# ECU_Checker_New.net
KiCad netlist of a schematic drawn in EAGLE
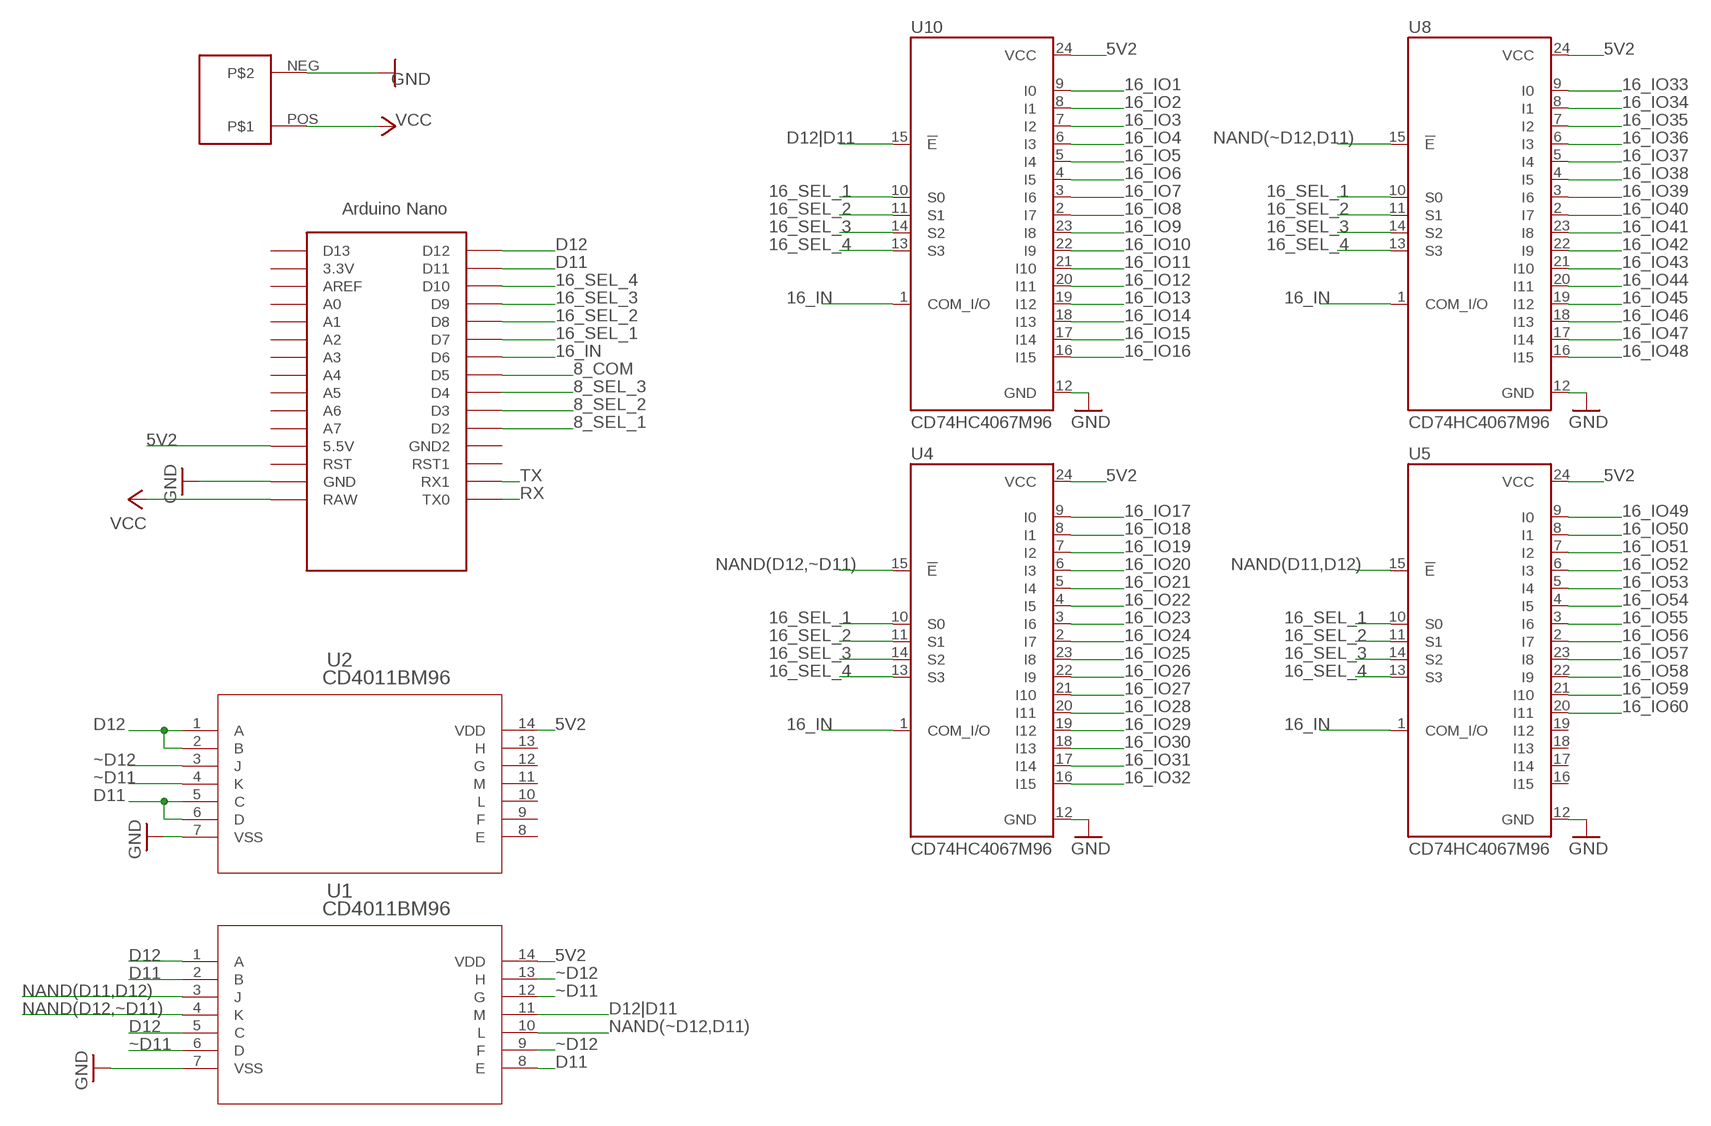
[diagram p0: schematic, sheet 1, part 1 of 2]
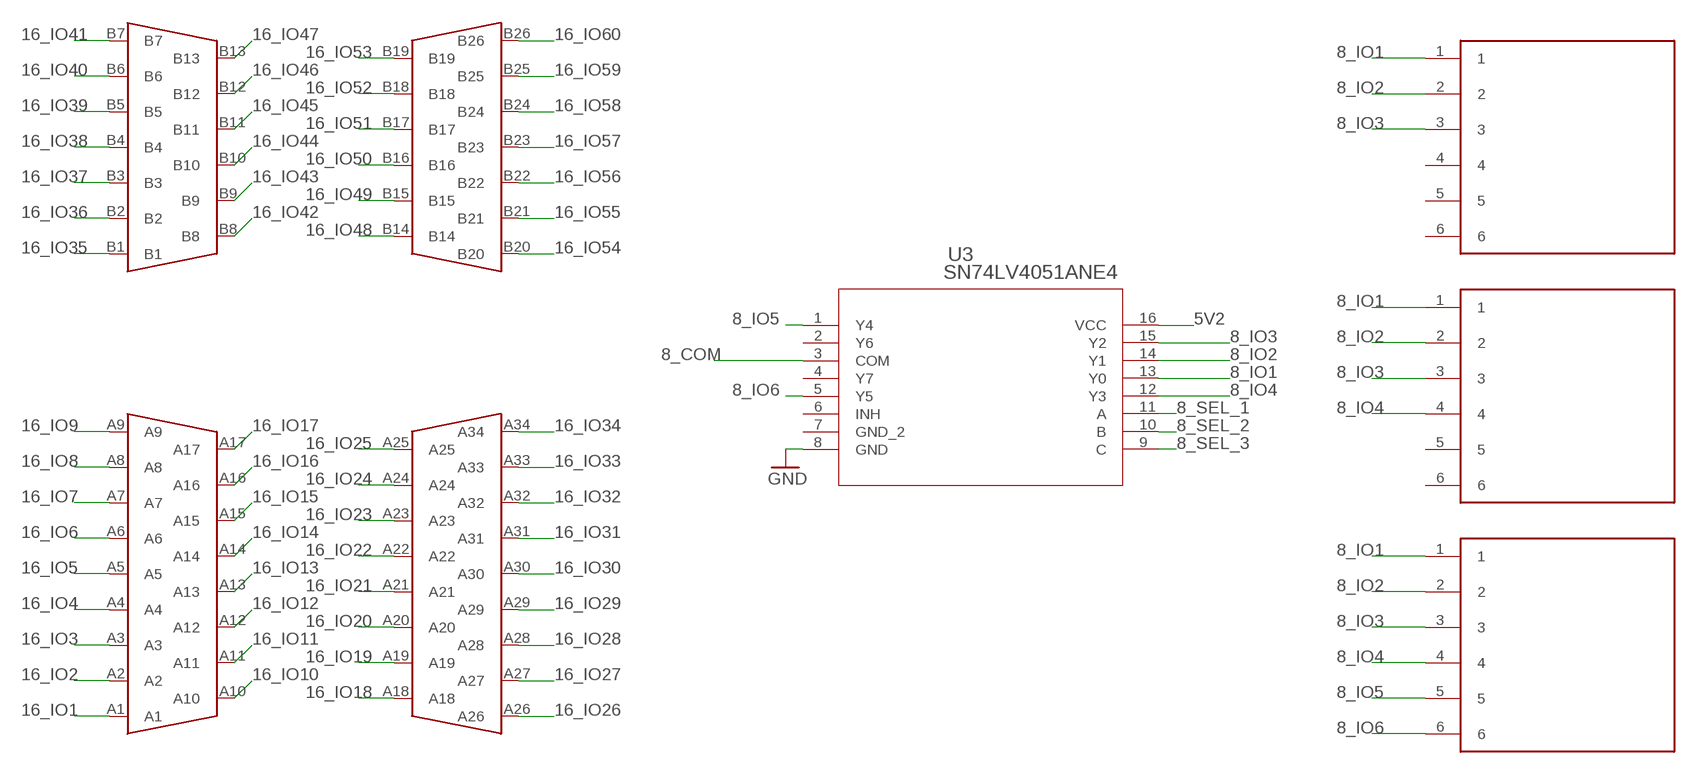
[diagram p1: schematic, sheet 1, part 2 of 2]

(export (version "E")
  (design (tool "Eeschema 10.0.6"))
  (components
    (comp (ref "U$2")
      (value "NANO")
      (footprint "eagle-import:NANO")
      (libsource (lib "eagle-import") (part "NANO"))
    )
    (comp (ref "U$3")
      (value "DTM_CON")
      (footprint "eagle-import:DTM_CON_F")
      (libsource (lib "eagle-import") (part "DTM_CON"))
    )
    (comp (ref "U$4")
      (value "BATTERY")
      (footprint "eagle-import:BATTERY_F")
      (libsource (lib "eagle-import") (part "BATTERY"))
    )
    (comp (ref "U$5")
      (value "DTM_CON")
      (footprint "eagle-import:DTM_CON_F")
      (libsource (lib "eagle-import") (part "DTM_CON"))
    )
    (comp (ref "U$6")
      (value "DTM_CON")
      (footprint "eagle-import:DTM_CON_F")
      (libsource (lib "eagle-import") (part "DTM_CON"))
    )
    (comp (ref "U$7")
      (value "MOTEC_400_CON")
      (footprint "eagle-import:MOTEC_400_CON_F")
      (libsource (lib "eagle-import") (part "MOTEC_400_CON"))
    )
    (comp (ref "U1")
      (value "CD4011BM96")
      (footprint "eagle-import:D14")
      (libsource (lib "eagle-import") (part "CD4011BM96"))
    )
    (comp (ref "U2")
      (value "CD4011BM96")
      (footprint "eagle-import:D14")
      (libsource (lib "eagle-import") (part "CD4011BM96"))
    )
    (comp (ref "U3")
      (value "SN74LV4051ANE4")
      (footprint "eagle-import:N16")
      (libsource (lib "eagle-import") (part "SN74LV4051ANE4"))
    )
    (comp (ref "U4")
      (value "CD74HC4067M96")
      (footprint "eagle-import:SOIC127P1030X265-24N")
      (fields (field (name "MF") "Texas Instruments"))
      (libsource (lib "eagle-import") (part "CD74HC4067M96"))
    )
    (comp (ref "U5")
      (value "CD74HC4067M96")
      (footprint "eagle-import:SOIC127P1030X265-24N")
      (fields (field (name "MF") "Texas Instruments"))
      (libsource (lib "eagle-import") (part "CD74HC4067M96"))
    )
    (comp (ref "U8")
      (value "CD74HC4067M96")
      (footprint "eagle-import:SOIC127P1030X265-24N")
      (fields (field (name "MF") "Texas Instruments"))
      (libsource (lib "eagle-import") (part "CD74HC4067M96"))
    )
    (comp (ref "U10")
      (value "CD74HC4067M96")
      (footprint "eagle-import:SOIC127P1030X265-24N")
      (fields (field (name "MF") "Texas Instruments"))
      (libsource (lib "eagle-import") (part "CD74HC4067M96"))
    )
  )
  (nets
    (net (code "1") (name "/5V2") (class "Default")
      (node (ref "U$2") (pin "5V") (pinfunction "5.5V_5V") (pintype "bidirectional"))
      (node (ref "U1") (pin "14") (pinfunction "VDD_14") (pintype "passive"))
      (node (ref "U10") (pin "24") (pinfunction "VCC_24") (pintype "power_in"))
      (node (ref "U2") (pin "14") (pinfunction "VDD_14") (pintype "passive"))
      (node (ref "U3") (pin "16") (pinfunction "VCC_16") (pintype "power_in"))
      (node (ref "U4") (pin "24") (pinfunction "VCC_24") (pintype "power_in"))
      (node (ref "U5") (pin "24") (pinfunction "VCC_24") (pintype "power_in"))
      (node (ref "U8") (pin "24") (pinfunction "VCC_24") (pintype "power_in"))
    )
    (net (code "2") (name "/8_COM") (class "Default")
      (node (ref "U$2") (pin "D5") (pinfunction "D5_D5") (pintype "bidirectional"))
      (node (ref "U3") (pin "3") (pinfunction "COM_3") (pintype "input"))
    )
    (net (code "3") (name "/8_IO1") (class "Default")
      (node (ref "U$3") (pin "1") (pinfunction "1_1") (pintype "bidirectional"))
      (node (ref "U$5") (pin "1") (pinfunction "1_1") (pintype "bidirectional"))
      (node (ref "U$6") (pin "1") (pinfunction "1_1") (pintype "bidirectional"))
      (node (ref "U3") (pin "13") (pinfunction "Y0_13") (pintype "output"))
    )
    (net (code "4") (name "/8_IO2") (class "Default")
      (node (ref "U$3") (pin "2") (pinfunction "2_2") (pintype "bidirectional"))
      (node (ref "U$5") (pin "2") (pinfunction "2_2") (pintype "bidirectional"))
      (node (ref "U$6") (pin "2") (pinfunction "2_2") (pintype "bidirectional"))
      (node (ref "U3") (pin "14") (pinfunction "Y1_14") (pintype "output"))
    )
    (net (code "5") (name "/8_IO3") (class "Default")
      (node (ref "U$3") (pin "3") (pinfunction "3_3") (pintype "bidirectional"))
      (node (ref "U$5") (pin "3") (pinfunction "3_3") (pintype "bidirectional"))
      (node (ref "U$6") (pin "3") (pinfunction "3_3") (pintype "bidirectional"))
      (node (ref "U3") (pin "15") (pinfunction "Y2_15") (pintype "output"))
    )
    (net (code "6") (name "/8_IO4") (class "Default")
      (node (ref "U$5") (pin "4") (pinfunction "4_4") (pintype "bidirectional"))
      (node (ref "U$6") (pin "4") (pinfunction "4_4") (pintype "bidirectional"))
      (node (ref "U3") (pin "12") (pinfunction "Y3_12") (pintype "output"))
    )
    (net (code "7") (name "/8_IO5") (class "Default")
      (node (ref "U$6") (pin "5") (pinfunction "5_5") (pintype "bidirectional"))
      (node (ref "U3") (pin "1") (pinfunction "Y4_1") (pintype "output"))
    )
    (net (code "8") (name "/8_IO6") (class "Default")
      (node (ref "U$6") (pin "6") (pinfunction "6_6") (pintype "bidirectional"))
      (node (ref "U3") (pin "5") (pinfunction "Y5_5") (pintype "output"))
    )
    (net (code "9") (name "/8_SEL_1") (class "Default")
      (node (ref "U$2") (pin "D2") (pinfunction "D2_D2") (pintype "bidirectional"))
      (node (ref "U3") (pin "11") (pinfunction "A_11") (pintype "input"))
    )
    (net (code "10") (name "/8_SEL_2") (class "Default")
      (node (ref "U$2") (pin "D3") (pinfunction "D3_D3") (pintype "bidirectional"))
      (node (ref "U3") (pin "10") (pinfunction "B_10") (pintype "input"))
    )
    (net (code "11") (name "/8_SEL_3") (class "Default")
      (node (ref "U$2") (pin "D4") (pinfunction "D4_D4") (pintype "bidirectional"))
      (node (ref "U3") (pin "9") (pinfunction "C_9") (pintype "input"))
    )
    (net (code "12") (name "/16_IN") (class "Default")
      (node (ref "U$2") (pin "D6") (pinfunction "D6_D6") (pintype "bidirectional"))
      (node (ref "U10") (pin "1") (pinfunction "COM_I/O_1") (pintype "bidirectional"))
      (node (ref "U4") (pin "1") (pinfunction "COM_I/O_1") (pintype "bidirectional"))
      (node (ref "U5") (pin "1") (pinfunction "COM_I/O_1") (pintype "bidirectional"))
      (node (ref "U8") (pin "1") (pinfunction "COM_I/O_1") (pintype "bidirectional"))
    )
    (net (code "13") (name "/16_IO1") (class "Default")
      (node (ref "U$7") (pin "A1") (pinfunction "A1_A1") (pintype "bidirectional"))
      (node (ref "U10") (pin "9") (pinfunction "I0_9") (pintype "bidirectional"))
    )
    (net (code "14") (name "/16_IO2") (class "Default")
      (node (ref "U$7") (pin "A2") (pinfunction "A2_A2") (pintype "bidirectional"))
      (node (ref "U10") (pin "8") (pinfunction "I1_8") (pintype "bidirectional"))
    )
    (net (code "15") (name "/16_IO3") (class "Default")
      (node (ref "U$7") (pin "A3") (pinfunction "A3_A3") (pintype "bidirectional"))
      (node (ref "U10") (pin "7") (pinfunction "I2_7") (pintype "bidirectional"))
    )
    (net (code "16") (name "/16_IO4") (class "Default")
      (node (ref "U$7") (pin "A4") (pinfunction "A4_A4") (pintype "bidirectional"))
      (node (ref "U10") (pin "6") (pinfunction "I3_6") (pintype "bidirectional"))
    )
    (net (code "17") (name "/16_IO5") (class "Default")
      (node (ref "U$7") (pin "A5") (pinfunction "A5_A5") (pintype "bidirectional"))
      (node (ref "U10") (pin "5") (pinfunction "I4_5") (pintype "bidirectional"))
    )
    (net (code "18") (name "/16_IO6") (class "Default")
      (node (ref "U$7") (pin "A6") (pinfunction "A6_A6") (pintype "bidirectional"))
      (node (ref "U10") (pin "4") (pinfunction "I5_4") (pintype "bidirectional"))
    )
    (net (code "19") (name "/16_IO7") (class "Default")
      (node (ref "U$7") (pin "A7") (pinfunction "A7_A7") (pintype "bidirectional"))
      (node (ref "U10") (pin "3") (pinfunction "I6_3") (pintype "bidirectional"))
    )
    (net (code "20") (name "/16_IO8") (class "Default")
      (node (ref "U$7") (pin "A8") (pinfunction "A8_A8") (pintype "bidirectional"))
      (node (ref "U10") (pin "2") (pinfunction "I7_2") (pintype "bidirectional"))
    )
    (net (code "21") (name "/16_IO9") (class "Default")
      (node (ref "U$7") (pin "A9") (pinfunction "A9_A9") (pintype "bidirectional"))
      (node (ref "U10") (pin "23") (pinfunction "I8_23") (pintype "bidirectional"))
    )
    (net (code "22") (name "/16_IO10") (class "Default")
      (node (ref "U$7") (pin "A10") (pinfunction "A10_A10") (pintype "bidirectional"))
      (node (ref "U10") (pin "22") (pinfunction "I9_22") (pintype "bidirectional"))
    )
    (net (code "23") (name "/16_IO11") (class "Default")
      (node (ref "U$7") (pin "A11") (pinfunction "A11_A11") (pintype "bidirectional"))
      (node (ref "U10") (pin "21") (pinfunction "I10_21") (pintype "bidirectional"))
    )
    (net (code "24") (name "/16_IO12") (class "Default")
      (node (ref "U$7") (pin "A12") (pinfunction "A12_A12") (pintype "bidirectional"))
      (node (ref "U10") (pin "20") (pinfunction "I11_20") (pintype "bidirectional"))
    )
    (net (code "25") (name "/16_IO13") (class "Default")
      (node (ref "U$7") (pin "A13") (pinfunction "A13_A13") (pintype "bidirectional"))
      (node (ref "U10") (pin "19") (pinfunction "I12_19") (pintype "bidirectional"))
    )
    (net (code "26") (name "/16_IO14") (class "Default")
      (node (ref "U$7") (pin "A14") (pinfunction "A14_A14") (pintype "bidirectional"))
      (node (ref "U10") (pin "18") (pinfunction "I13_18") (pintype "bidirectional"))
    )
    (net (code "27") (name "/16_IO15") (class "Default")
      (node (ref "U$7") (pin "A15") (pinfunction "A15_A15") (pintype "bidirectional"))
      (node (ref "U10") (pin "17") (pinfunction "I14_17") (pintype "bidirectional"))
    )
    (net (code "28") (name "/16_IO16") (class "Default")
      (node (ref "U$7") (pin "A16") (pinfunction "A16_A16") (pintype "bidirectional"))
      (node (ref "U10") (pin "16") (pinfunction "I15_16") (pintype "bidirectional"))
    )
    (net (code "29") (name "/16_IO17") (class "Default")
      (node (ref "U$7") (pin "A17") (pinfunction "A17_A17") (pintype "bidirectional"))
      (node (ref "U4") (pin "9") (pinfunction "I0_9") (pintype "bidirectional"))
    )
    (net (code "30") (name "/16_IO18") (class "Default")
      (node (ref "U$7") (pin "A18") (pinfunction "A18_A18") (pintype "bidirectional"))
      (node (ref "U4") (pin "8") (pinfunction "I1_8") (pintype "bidirectional"))
    )
    (net (code "31") (name "/16_IO19") (class "Default")
      (node (ref "U$7") (pin "A19") (pinfunction "A19_A19") (pintype "bidirectional"))
      (node (ref "U4") (pin "7") (pinfunction "I2_7") (pintype "bidirectional"))
    )
    (net (code "32") (name "/16_IO20") (class "Default")
      (node (ref "U$7") (pin "A20") (pinfunction "A20_A20") (pintype "bidirectional"))
      (node (ref "U4") (pin "6") (pinfunction "I3_6") (pintype "bidirectional"))
    )
    (net (code "33") (name "/16_IO21") (class "Default")
      (node (ref "U$7") (pin "A21") (pinfunction "A21_A21") (pintype "bidirectional"))
      (node (ref "U4") (pin "5") (pinfunction "I4_5") (pintype "bidirectional"))
    )
    (net (code "34") (name "/16_IO22") (class "Default")
      (node (ref "U$7") (pin "A22") (pinfunction "A22_A22") (pintype "bidirectional"))
      (node (ref "U4") (pin "4") (pinfunction "I5_4") (pintype "bidirectional"))
    )
    (net (code "35") (name "/16_IO23") (class "Default")
      (node (ref "U$7") (pin "A23") (pinfunction "A23_A23") (pintype "bidirectional"))
      (node (ref "U4") (pin "3") (pinfunction "I6_3") (pintype "bidirectional"))
    )
    (net (code "36") (name "/16_IO24") (class "Default")
      (node (ref "U$7") (pin "A24") (pinfunction "A24_A24") (pintype "bidirectional"))
      (node (ref "U4") (pin "2") (pinfunction "I7_2") (pintype "bidirectional"))
    )
    (net (code "37") (name "/16_IO25") (class "Default")
      (node (ref "U$7") (pin "A25") (pinfunction "A25_A25") (pintype "bidirectional"))
      (node (ref "U4") (pin "23") (pinfunction "I8_23") (pintype "bidirectional"))
    )
    (net (code "38") (name "/16_IO26") (class "Default")
      (node (ref "U$7") (pin "A26") (pinfunction "A26_A26") (pintype "bidirectional"))
      (node (ref "U4") (pin "22") (pinfunction "I9_22") (pintype "bidirectional"))
    )
    (net (code "39") (name "/16_IO27") (class "Default")
      (node (ref "U$7") (pin "A27") (pinfunction "A27_A27") (pintype "bidirectional"))
      (node (ref "U4") (pin "21") (pinfunction "I10_21") (pintype "bidirectional"))
    )
    (net (code "40") (name "/16_IO28") (class "Default")
      (node (ref "U$7") (pin "A28") (pinfunction "A28_A28") (pintype "bidirectional"))
      (node (ref "U4") (pin "20") (pinfunction "I11_20") (pintype "bidirectional"))
    )
    (net (code "41") (name "/16_IO29") (class "Default")
      (node (ref "U$7") (pin "A29") (pinfunction "A29_A29") (pintype "bidirectional"))
      (node (ref "U4") (pin "19") (pinfunction "I12_19") (pintype "bidirectional"))
    )
    (net (code "42") (name "/16_IO30") (class "Default")
      (node (ref "U$7") (pin "A30") (pinfunction "A30_A30") (pintype "bidirectional"))
      (node (ref "U4") (pin "18") (pinfunction "I13_18") (pintype "bidirectional"))
    )
    (net (code "43") (name "/16_IO31") (class "Default")
      (node (ref "U$7") (pin "A31") (pinfunction "A31_A31") (pintype "bidirectional"))
      (node (ref "U4") (pin "17") (pinfunction "I14_17") (pintype "bidirectional"))
    )
    (net (code "44") (name "/16_IO32") (class "Default")
      (node (ref "U$7") (pin "A32") (pinfunction "A32_A32") (pintype "bidirectional"))
      (node (ref "U4") (pin "16") (pinfunction "I15_16") (pintype "bidirectional"))
    )
    (net (code "45") (name "/16_IO33") (class "Default")
      (node (ref "U$7") (pin "A33") (pinfunction "A33_A33") (pintype "bidirectional"))
      (node (ref "U8") (pin "9") (pinfunction "I0_9") (pintype "bidirectional"))
    )
    (net (code "46") (name "/16_IO34") (class "Default")
      (node (ref "U$7") (pin "A34") (pinfunction "A34_A34") (pintype "bidirectional"))
      (node (ref "U8") (pin "8") (pinfunction "I1_8") (pintype "bidirectional"))
    )
    (net (code "47") (name "/16_IO35") (class "Default")
      (node (ref "U$7") (pin "B1") (pinfunction "B1_B1") (pintype "bidirectional"))
      (node (ref "U8") (pin "7") (pinfunction "I2_7") (pintype "bidirectional"))
    )
    (net (code "48") (name "/16_IO36") (class "Default")
      (node (ref "U$7") (pin "B2") (pinfunction "B2_B2") (pintype "bidirectional"))
      (node (ref "U8") (pin "6") (pinfunction "I3_6") (pintype "bidirectional"))
    )
    (net (code "49") (name "/16_IO37") (class "Default")
      (node (ref "U$7") (pin "B3") (pinfunction "B3_B3") (pintype "bidirectional"))
      (node (ref "U8") (pin "5") (pinfunction "I4_5") (pintype "bidirectional"))
    )
    (net (code "50") (name "/16_IO38") (class "Default")
      (node (ref "U$7") (pin "B4") (pinfunction "B4_B4") (pintype "bidirectional"))
      (node (ref "U8") (pin "4") (pinfunction "I5_4") (pintype "bidirectional"))
    )
    (net (code "51") (name "/16_IO39") (class "Default")
      (node (ref "U$7") (pin "B5") (pinfunction "B5_B5") (pintype "bidirectional"))
      (node (ref "U8") (pin "3") (pinfunction "I6_3") (pintype "bidirectional"))
    )
    (net (code "52") (name "/16_IO40") (class "Default")
      (node (ref "U$7") (pin "B6") (pinfunction "B6_B6") (pintype "bidirectional"))
      (node (ref "U8") (pin "2") (pinfunction "I7_2") (pintype "bidirectional"))
    )
    (net (code "53") (name "/16_IO41") (class "Default")
      (node (ref "U$7") (pin "B7") (pinfunction "B7_B7") (pintype "bidirectional"))
      (node (ref "U8") (pin "23") (pinfunction "I8_23") (pintype "bidirectional"))
    )
    (net (code "54") (name "/16_IO42") (class "Default")
      (node (ref "U$7") (pin "B8") (pinfunction "B8_B8") (pintype "bidirectional"))
      (node (ref "U8") (pin "22") (pinfunction "I9_22") (pintype "bidirectional"))
    )
    (net (code "55") (name "/16_IO43") (class "Default")
      (node (ref "U$7") (pin "B9") (pinfunction "B9_B9") (pintype "bidirectional"))
      (node (ref "U8") (pin "21") (pinfunction "I10_21") (pintype "bidirectional"))
    )
    (net (code "56") (name "/16_IO44") (class "Default")
      (node (ref "U$7") (pin "B10") (pinfunction "B10_B10") (pintype "bidirectional"))
      (node (ref "U8") (pin "20") (pinfunction "I11_20") (pintype "bidirectional"))
    )
    (net (code "57") (name "/16_IO45") (class "Default")
      (node (ref "U$7") (pin "B11") (pinfunction "B11_B11") (pintype "bidirectional"))
      (node (ref "U8") (pin "19") (pinfunction "I12_19") (pintype "bidirectional"))
    )
    (net (code "58") (name "/16_IO46") (class "Default")
      (node (ref "U$7") (pin "B12") (pinfunction "B12_B12") (pintype "bidirectional"))
      (node (ref "U8") (pin "18") (pinfunction "I13_18") (pintype "bidirectional"))
    )
    (net (code "59") (name "/16_IO47") (class "Default")
      (node (ref "U$7") (pin "B13") (pinfunction "B13_B13") (pintype "bidirectional"))
      (node (ref "U8") (pin "17") (pinfunction "I14_17") (pintype "bidirectional"))
    )
    (net (code "60") (name "/16_IO48") (class "Default")
      (node (ref "U$7") (pin "B14") (pinfunction "B14_B14") (pintype "bidirectional"))
      (node (ref "U8") (pin "16") (pinfunction "I15_16") (pintype "bidirectional"))
    )
    (net (code "61") (name "/16_IO49") (class "Default")
      (node (ref "U$7") (pin "B15") (pinfunction "B15_B15") (pintype "bidirectional"))
      (node (ref "U5") (pin "9") (pinfunction "I0_9") (pintype "bidirectional"))
    )
    (net (code "62") (name "/16_IO50") (class "Default")
      (node (ref "U$7") (pin "B16") (pinfunction "B16_B16") (pintype "bidirectional"))
      (node (ref "U5") (pin "8") (pinfunction "I1_8") (pintype "bidirectional"))
    )
    (net (code "63") (name "/16_IO51") (class "Default")
      (node (ref "U$7") (pin "B17") (pinfunction "B17_B17") (pintype "bidirectional"))
      (node (ref "U5") (pin "7") (pinfunction "I2_7") (pintype "bidirectional"))
    )
    (net (code "64") (name "/16_IO52") (class "Default")
      (node (ref "U$7") (pin "B18") (pinfunction "B18_B18") (pintype "bidirectional"))
      (node (ref "U5") (pin "6") (pinfunction "I3_6") (pintype "bidirectional"))
    )
    (net (code "65") (name "/16_IO53") (class "Default")
      (node (ref "U$7") (pin "B19") (pinfunction "B19_B19") (pintype "bidirectional"))
      (node (ref "U5") (pin "5") (pinfunction "I4_5") (pintype "bidirectional"))
    )
    (net (code "66") (name "/16_IO54") (class "Default")
      (node (ref "U$7") (pin "B20") (pinfunction "B20_B20") (pintype "bidirectional"))
      (node (ref "U5") (pin "4") (pinfunction "I5_4") (pintype "bidirectional"))
    )
    (net (code "67") (name "/16_IO55") (class "Default")
      (node (ref "U$7") (pin "B21") (pinfunction "B21_B21") (pintype "bidirectional"))
      (node (ref "U5") (pin "3") (pinfunction "I6_3") (pintype "bidirectional"))
    )
    (net (code "68") (name "/16_IO56") (class "Default")
      (node (ref "U$7") (pin "B22") (pinfunction "B22_B22") (pintype "bidirectional"))
      (node (ref "U5") (pin "2") (pinfunction "I7_2") (pintype "bidirectional"))
    )
    (net (code "69") (name "/16_IO57") (class "Default")
      (node (ref "U$7") (pin "B23") (pinfunction "B23_B23") (pintype "bidirectional"))
      (node (ref "U5") (pin "23") (pinfunction "I8_23") (pintype "bidirectional"))
    )
    (net (code "70") (name "/16_IO58") (class "Default")
      (node (ref "U$7") (pin "B24") (pinfunction "B24_B24") (pintype "bidirectional"))
      (node (ref "U5") (pin "22") (pinfunction "I9_22") (pintype "bidirectional"))
    )
    (net (code "71") (name "/16_IO59") (class "Default")
      (node (ref "U$7") (pin "B25") (pinfunction "B25_B25") (pintype "bidirectional"))
      (node (ref "U5") (pin "21") (pinfunction "I10_21") (pintype "bidirectional"))
    )
    (net (code "72") (name "/16_IO60") (class "Default")
      (node (ref "U$7") (pin "B26") (pinfunction "B26_B26") (pintype "bidirectional"))
      (node (ref "U5") (pin "20") (pinfunction "I11_20") (pintype "bidirectional"))
    )
    (net (code "73") (name "/16_SEL_1") (class "Default")
      (node (ref "U$2") (pin "D7") (pinfunction "D7_D7") (pintype "bidirectional"))
      (node (ref "U10") (pin "10") (pinfunction "S0_10") (pintype "input"))
      (node (ref "U4") (pin "10") (pinfunction "S0_10") (pintype "input"))
      (node (ref "U5") (pin "10") (pinfunction "S0_10") (pintype "input"))
      (node (ref "U8") (pin "10") (pinfunction "S0_10") (pintype "input"))
    )
    (net (code "74") (name "/16_SEL_2") (class "Default")
      (node (ref "U$2") (pin "D8") (pinfunction "D8_D8") (pintype "bidirectional"))
      (node (ref "U10") (pin "11") (pinfunction "S1_11") (pintype "input"))
      (node (ref "U4") (pin "11") (pinfunction "S1_11") (pintype "input"))
      (node (ref "U5") (pin "11") (pinfunction "S1_11") (pintype "input"))
      (node (ref "U8") (pin "11") (pinfunction "S1_11") (pintype "input"))
    )
    (net (code "75") (name "/16_SEL_3") (class "Default")
      (node (ref "U$2") (pin "D9") (pinfunction "D9_D9") (pintype "bidirectional"))
      (node (ref "U10") (pin "14") (pinfunction "S2_14") (pintype "input"))
      (node (ref "U4") (pin "14") (pinfunction "S2_14") (pintype "input"))
      (node (ref "U5") (pin "14") (pinfunction "S2_14") (pintype "input"))
      (node (ref "U8") (pin "14") (pinfunction "S2_14") (pintype "input"))
    )
    (net (code "76") (name "/16_SEL_4") (class "Default")
      (node (ref "U$2") (pin "D10") (pinfunction "D10_D10") (pintype "bidirectional"))
      (node (ref "U10") (pin "13") (pinfunction "S3_13") (pintype "input"))
      (node (ref "U4") (pin "13") (pinfunction "S3_13") (pintype "input"))
      (node (ref "U5") (pin "13") (pinfunction "S3_13") (pintype "input"))
      (node (ref "U8") (pin "13") (pinfunction "S3_13") (pintype "input"))
    )
    (net (code "77") (name "/D11") (class "Default")
      (node (ref "U$2") (pin "D11") (pinfunction "D11_D11") (pintype "bidirectional"))
      (node (ref "U1") (pin "2") (pinfunction "B_2") (pintype "input"))
      (node (ref "U1") (pin "8") (pinfunction "E_8") (pintype "input"))
      (node (ref "U2") (pin "5") (pinfunction "C_5") (pintype "input"))
      (node (ref "U2") (pin "6") (pinfunction "D_6") (pintype "input"))
    )
    (net (code "78") (name "/D12") (class "Default")
      (node (ref "U$2") (pin "D12") (pinfunction "D12_D12") (pintype "bidirectional"))
      (node (ref "U1") (pin "1") (pinfunction "A_1") (pintype "input"))
      (node (ref "U1") (pin "5") (pinfunction "C_5") (pintype "input"))
      (node (ref "U2") (pin "1") (pinfunction "A_1") (pintype "input"))
      (node (ref "U2") (pin "2") (pinfunction "B_2") (pintype "input"))
    )
    (net (code "79") (name "/D12|D11") (class "Default")
      (node (ref "U1") (pin "11") (pinfunction "M_11") (pintype "output"))
      (node (ref "U10") (pin "15") (pinfunction "~{E}_15") (pintype "input"))
    )
    (net (code "80") (name "/GND_2") (class "Default")
      (node (ref "U3") (pin "7") (pinfunction "GND_2_7") (pintype "power_in"))
    )
    (net (code "81") (name "/NAND(D11,D12)") (class "Default")
      (node (ref "U1") (pin "3") (pinfunction "J_3") (pintype "output"))
      (node (ref "U5") (pin "15") (pinfunction "~{E}_15") (pintype "input"))
    )
    (net (code "82") (name "/NAND(D12,~{D11})") (class "Default")
      (node (ref "U1") (pin "4") (pinfunction "K_4") (pintype "output"))
      (node (ref "U4") (pin "15") (pinfunction "~{E}_15") (pintype "input"))
    )
    (net (code "83") (name "/NAND(~{D12,D11})") (class "Default")
      (node (ref "U1") (pin "10") (pinfunction "L_10") (pintype "output"))
      (node (ref "U8") (pin "15") (pinfunction "~{E}_15") (pintype "input"))
    )
    (net (code "84") (name "/RX") (class "Default")
      (node (ref "U$2") (pin "TX0") (pinfunction "TX0_TX0") (pintype "bidirectional"))
    )
    (net (code "85") (name "/TX") (class "Default")
      (node (ref "U$2") (pin "RX1") (pinfunction "RX1_RX1") (pintype "bidirectional"))
    )
    (net (code "86") (name "/~{D11}") (class "Default")
      (node (ref "U1") (pin "12") (pinfunction "G_12") (pintype "input"))
      (node (ref "U1") (pin "6") (pinfunction "D_6") (pintype "input"))
      (node (ref "U2") (pin "4") (pinfunction "K_4") (pintype "output"))
    )
    (net (code "87") (name "/~{D12}") (class "Default")
      (node (ref "U1") (pin "13") (pinfunction "H_13") (pintype "input"))
      (node (ref "U1") (pin "9") (pinfunction "F_9") (pintype "input"))
      (node (ref "U2") (pin "3") (pinfunction "J_3") (pintype "output"))
    )
    (net (code "88") (name "GND") (class "Default")
      (node (ref "U$2") (pin "GND") (pinfunction "GND_GND") (pintype "bidirectional"))
      (node (ref "U$4") (pin "NEG") (pinfunction "P$2_NEG") (pintype "bidirectional"))
      (node (ref "U1") (pin "7") (pinfunction "VSS_7") (pintype "passive"))
      (node (ref "U10") (pin "12") (pinfunction "GND_12") (pintype "power_in"))
      (node (ref "U2") (pin "7") (pinfunction "VSS_7") (pintype "passive"))
      (node (ref "U3") (pin "8") (pinfunction "GND_8") (pintype "power_in"))
      (node (ref "U4") (pin "12") (pinfunction "GND_12") (pintype "power_in"))
      (node (ref "U5") (pin "12") (pinfunction "GND_12") (pintype "power_in"))
      (node (ref "U8") (pin "12") (pinfunction "GND_12") (pintype "power_in"))
    )
    (net (code "89") (name "VCC") (class "Default")
      (node (ref "U$2") (pin "RAW") (pinfunction "RAW_RAW") (pintype "bidirectional"))
      (node (ref "U$4") (pin "POS") (pinfunction "P$1_POS") (pintype "bidirectional"))
    )
    (net (code "90") (name "unconnected-(U$2-GND2-PadGND1)") (class "Default")
      (node (ref "U$2") (pin "GND1") (pinfunction "GND2_GND1") (pintype "bidirectional"))
    )
    (net (code "91") (name "unconnected-(U$2-Pad3.3V)") (class "Default")
      (node (ref "U$2") (pin "3.3V") (pinfunction "3.3V_3.3V") (pintype "bidirectional"))
    )
    (net (code "92") (name "unconnected-(U$2-PadA0)") (class "Default")
      (node (ref "U$2") (pin "A0") (pinfunction "A0_A0") (pintype "bidirectional"))
    )
    (net (code "93") (name "unconnected-(U$2-PadA1)") (class "Default")
      (node (ref "U$2") (pin "A1") (pinfunction "A1_A1") (pintype "bidirectional"))
    )
    (net (code "94") (name "unconnected-(U$2-PadA2)") (class "Default")
      (node (ref "U$2") (pin "A2") (pinfunction "A2_A2") (pintype "bidirectional"))
    )
    (net (code "95") (name "unconnected-(U$2-PadA3)") (class "Default")
      (node (ref "U$2") (pin "A3") (pinfunction "A3_A3") (pintype "bidirectional"))
    )
    (net (code "96") (name "unconnected-(U$2-PadA4)") (class "Default")
      (node (ref "U$2") (pin "A4") (pinfunction "A4_A4") (pintype "bidirectional"))
    )
    (net (code "97") (name "unconnected-(U$2-PadA5)") (class "Default")
      (node (ref "U$2") (pin "A5") (pinfunction "A5_A5") (pintype "bidirectional"))
    )
    (net (code "98") (name "unconnected-(U$2-PadA6)") (class "Default")
      (node (ref "U$2") (pin "A6") (pinfunction "A6_A6") (pintype "bidirectional"))
    )
    (net (code "99") (name "unconnected-(U$2-PadA7)") (class "Default")
      (node (ref "U$2") (pin "A7") (pinfunction "A7_A7") (pintype "bidirectional"))
    )
    (net (code "100") (name "unconnected-(U$2-PadAREF)") (class "Default")
      (node (ref "U$2") (pin "AREF") (pinfunction "AREF_AREF") (pintype "bidirectional"))
    )
    (net (code "101") (name "unconnected-(U$2-PadD13)") (class "Default")
      (node (ref "U$2") (pin "D13") (pinfunction "D13_D13") (pintype "bidirectional"))
    )
    (net (code "102") (name "unconnected-(U$2-PadICSP1)") (class "Default")
      (node (ref "U$2") (pin "ICSP1") (pinfunction "ICSP1_ICSP1") (pintype "bidirectional"))
    )
    (net (code "103") (name "unconnected-(U$2-PadICSP2)") (class "Default")
      (node (ref "U$2") (pin "ICSP2") (pinfunction "ICSP2_ICSP2") (pintype "bidirectional"))
    )
    (net (code "104") (name "unconnected-(U$2-PadICSP3)") (class "Default")
      (node (ref "U$2") (pin "ICSP3") (pinfunction "ICSP3_ICSP3") (pintype "bidirectional"))
    )
    (net (code "105") (name "unconnected-(U$2-PadICSP4)") (class "Default")
      (node (ref "U$2") (pin "ICSP4") (pinfunction "ICSP4_ICSP4") (pintype "bidirectional"))
    )
    (net (code "106") (name "unconnected-(U$2-PadICSP5)") (class "Default")
      (node (ref "U$2") (pin "ICSP5") (pinfunction "ICSP5_ICSP5") (pintype "bidirectional"))
    )
    (net (code "107") (name "unconnected-(U$2-PadICSP6)") (class "Default")
      (node (ref "U$2") (pin "ICSP6") (pinfunction "ICSP6_ICSP6") (pintype "bidirectional"))
    )
    (net (code "108") (name "unconnected-(U$2-PadRST)") (class "Default")
      (node (ref "U$2") (pin "RST") (pinfunction "RST_RST") (pintype "bidirectional"))
    )
    (net (code "109") (name "unconnected-(U$2-PadRST1)") (class "Default")
      (node (ref "U$2") (pin "RST1") (pinfunction "RST1_RST1") (pintype "bidirectional"))
    )
    (net (code "110") (name "unconnected-(U$3-Pad4)") (class "Default")
      (node (ref "U$3") (pin "4") (pinfunction "4_4") (pintype "bidirectional"))
    )
    (net (code "111") (name "unconnected-(U$3-Pad5)") (class "Default")
      (node (ref "U$3") (pin "5") (pinfunction "5_5") (pintype "bidirectional"))
    )
    (net (code "112") (name "unconnected-(U$3-Pad6)") (class "Default")
      (node (ref "U$3") (pin "6") (pinfunction "6_6") (pintype "bidirectional"))
    )
    (net (code "113") (name "unconnected-(U$5-Pad5)") (class "Default")
      (node (ref "U$5") (pin "5") (pinfunction "5_5") (pintype "bidirectional"))
    )
    (net (code "114") (name "unconnected-(U$5-Pad6)") (class "Default")
      (node (ref "U$5") (pin "6") (pinfunction "6_6") (pintype "bidirectional"))
    )
    (net (code "115") (name "unconnected-(U2-E-Pad8)") (class "Default")
      (node (ref "U2") (pin "8") (pinfunction "E_8") (pintype "input"))
    )
    (net (code "116") (name "unconnected-(U2-F-Pad9)") (class "Default")
      (node (ref "U2") (pin "9") (pinfunction "F_9") (pintype "input"))
    )
    (net (code "117") (name "unconnected-(U2-G-Pad12)") (class "Default")
      (node (ref "U2") (pin "12") (pinfunction "G_12") (pintype "input"))
    )
    (net (code "118") (name "unconnected-(U2-H-Pad13)") (class "Default")
      (node (ref "U2") (pin "13") (pinfunction "H_13") (pintype "input"))
    )
    (net (code "119") (name "unconnected-(U2-L-Pad10)") (class "Default")
      (node (ref "U2") (pin "10") (pinfunction "L_10") (pintype "output"))
    )
    (net (code "120") (name "unconnected-(U2-M-Pad11)") (class "Default")
      (node (ref "U2") (pin "11") (pinfunction "M_11") (pintype "output"))
    )
    (net (code "121") (name "unconnected-(U3-INH-Pad6)") (class "Default")
      (node (ref "U3") (pin "6") (pinfunction "INH_6") (pintype "input"))
    )
    (net (code "122") (name "unconnected-(U3-Y6-Pad2)") (class "Default")
      (node (ref "U3") (pin "2") (pinfunction "Y6_2") (pintype "output"))
    )
    (net (code "123") (name "unconnected-(U3-Y7-Pad4)") (class "Default")
      (node (ref "U3") (pin "4") (pinfunction "Y7_4") (pintype "output"))
    )
    (net (code "124") (name "unconnected-(U5-I12-Pad19)") (class "Default")
      (node (ref "U5") (pin "19") (pinfunction "I12_19") (pintype "bidirectional"))
    )
    (net (code "125") (name "unconnected-(U5-I13-Pad18)") (class "Default")
      (node (ref "U5") (pin "18") (pinfunction "I13_18") (pintype "bidirectional"))
    )
    (net (code "126") (name "unconnected-(U5-I14-Pad17)") (class "Default")
      (node (ref "U5") (pin "17") (pinfunction "I14_17") (pintype "bidirectional"))
    )
    (net (code "127") (name "unconnected-(U5-I15-Pad16)") (class "Default")
      (node (ref "U5") (pin "16") (pinfunction "I15_16") (pintype "bidirectional"))
    )
  )
)
